# SODIMM.net
KiCad netlist of a schematic drawn in Altium Designer
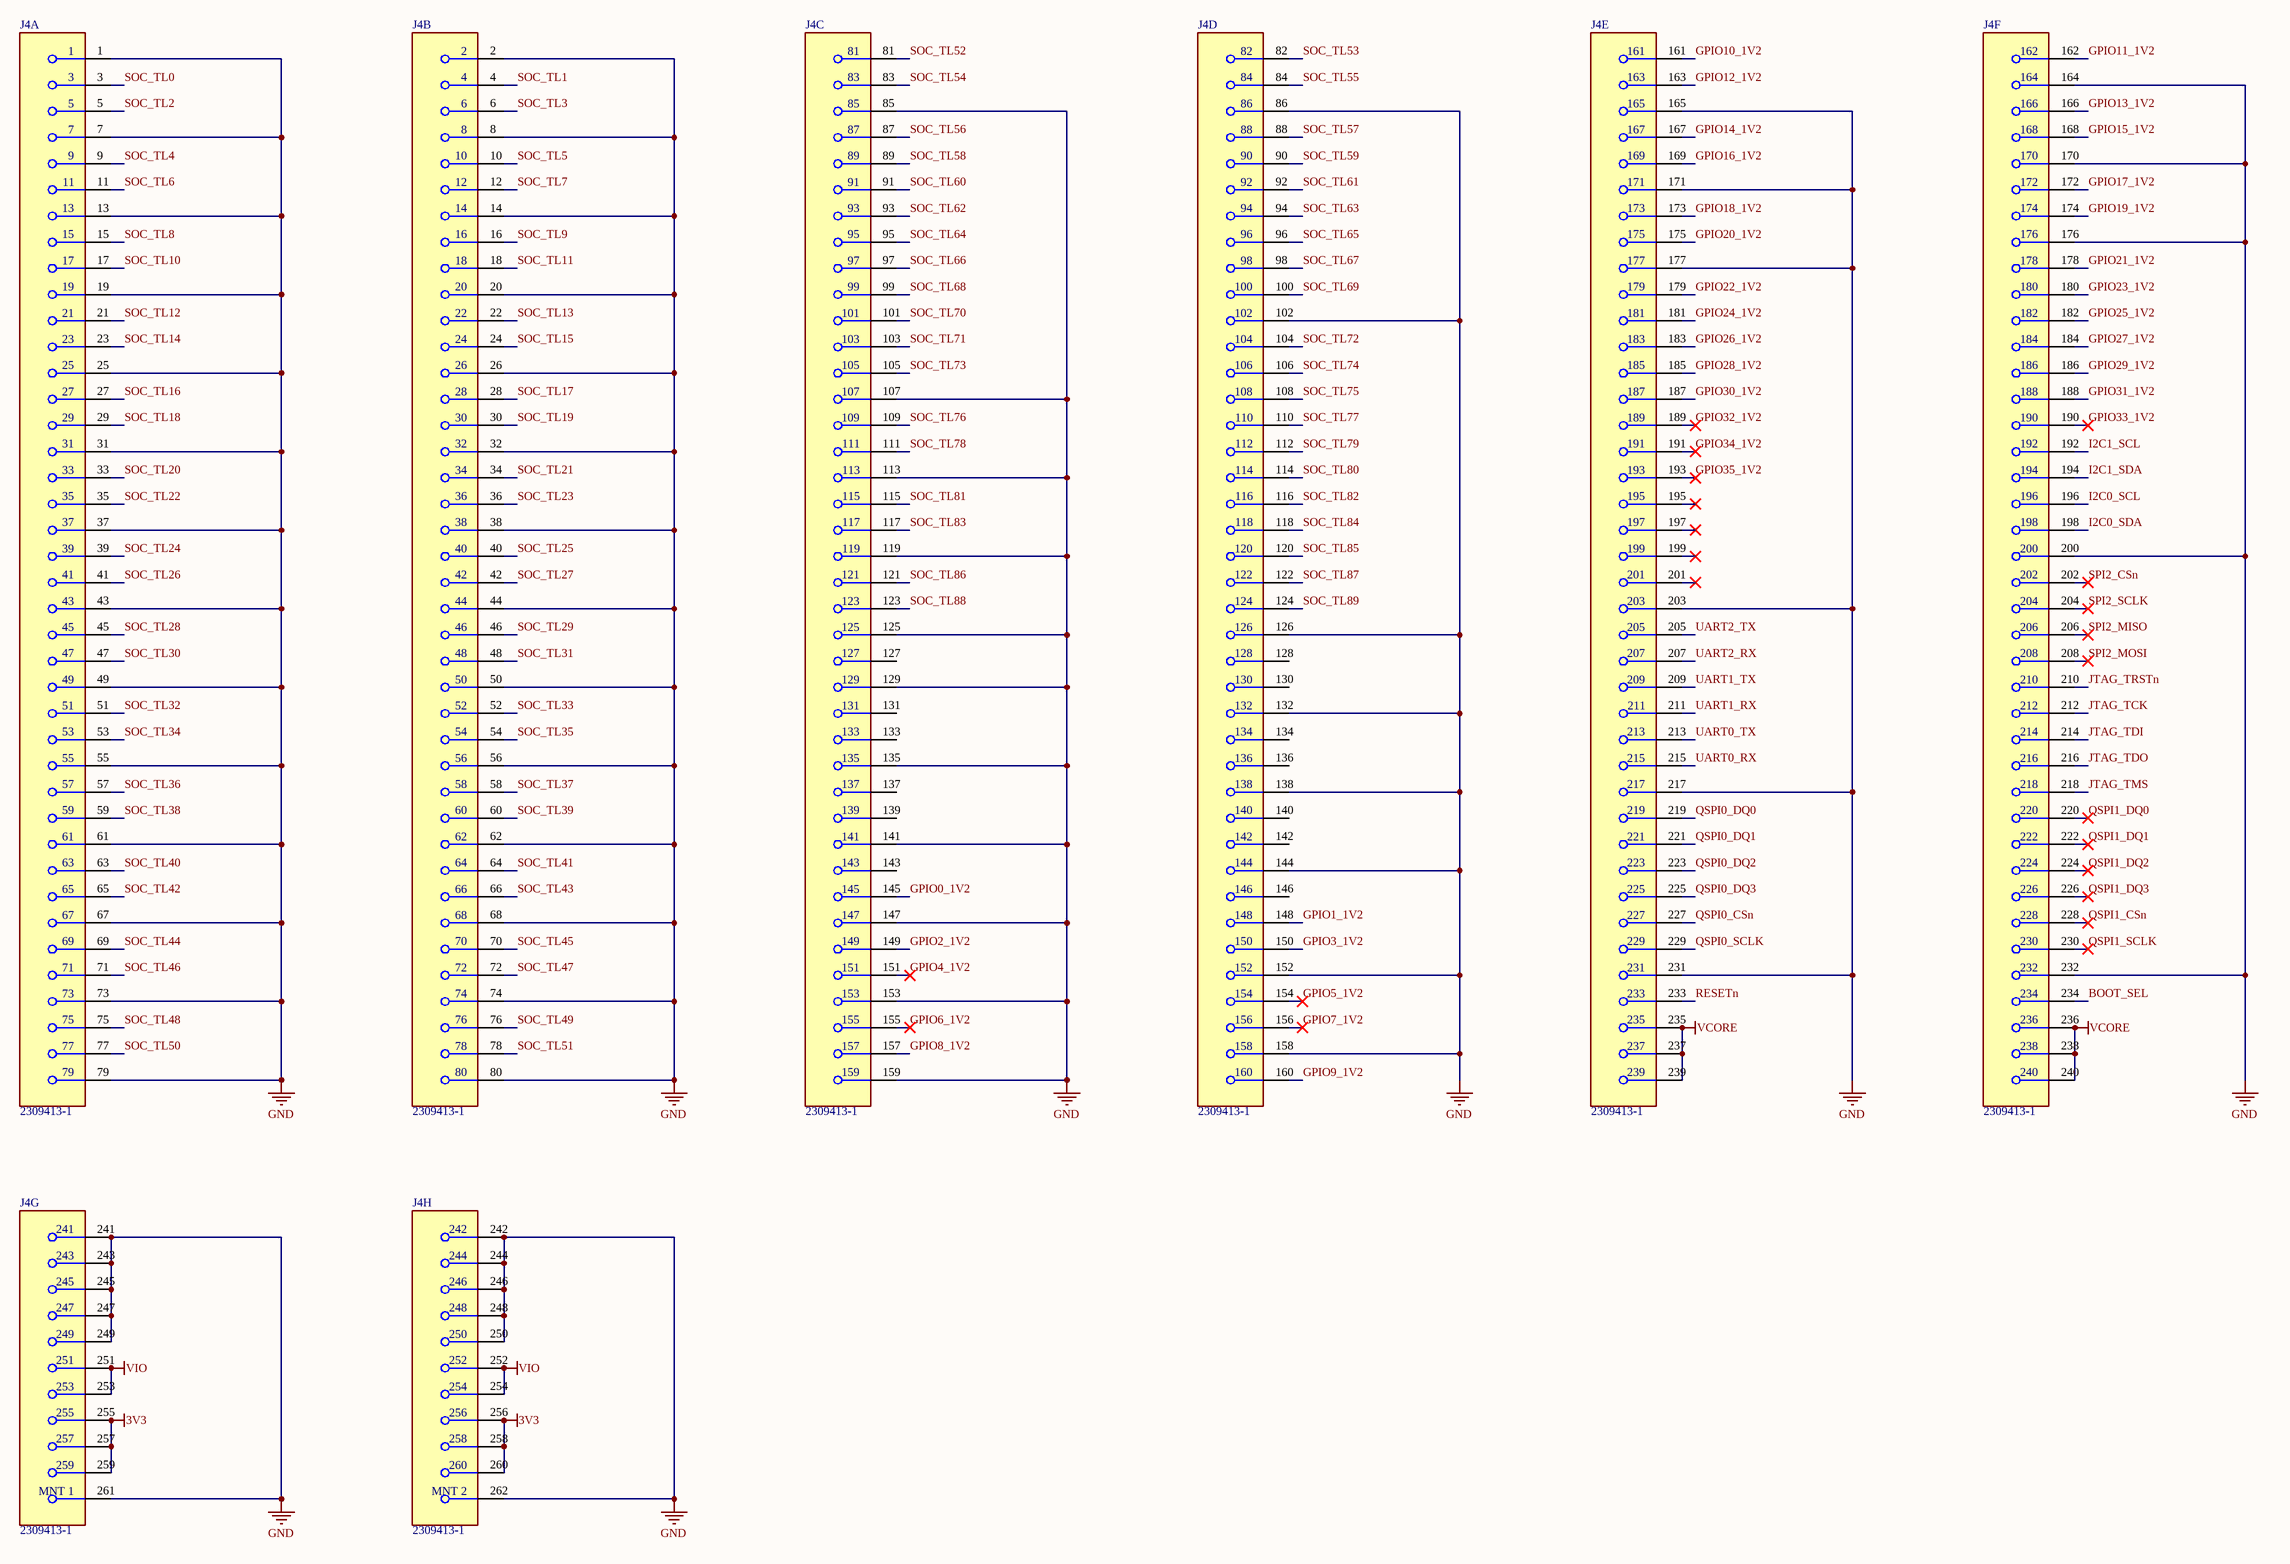
[diagram p0: SODIMM.SchDoc]

(export (version "E")
  (design (tool "Eeschema 10.0.6"))
  (components
    (comp (ref "J4")
      (value "2309413-1")
      (footprint "FP-2309413-1-MFG")
      (description "Memory Card Connector, DDR4, SODIMM, Cam-In Locking, 260 Contacts, Copper Alloy")
      (libsource (lib "UC Berkeley – EE194") (part "2309413-1"))
    )
  )
  (nets
    (net (code "1") (name "/BOOT_SEL") (class "Default")
      (node (ref "J4") (pin "234") (pinfunction "234_234") (pintype "passive"))
    )
    (net (code "2") (name "/GPIO0_1V2") (class "Default")
      (node (ref "J4") (pin "145") (pinfunction "145_145") (pintype "passive"))
    )
    (net (code "3") (name "/GPIO1_1V2") (class "Default")
      (node (ref "J4") (pin "148") (pinfunction "148_148") (pintype "passive"))
    )
    (net (code "4") (name "/GPIO2_1V2") (class "Default")
      (node (ref "J4") (pin "149") (pinfunction "149_149") (pintype "passive"))
    )
    (net (code "5") (name "/GPIO3_1V2") (class "Default")
      (node (ref "J4") (pin "150") (pinfunction "150_150") (pintype "passive"))
    )
    (net (code "6") (name "/GPIO4_1V2") (class "Default")
      (node (ref "J4") (pin "151") (pinfunction "151_151") (pintype "passive+no_connect"))
    )
    (net (code "7") (name "/GPIO5_1V2") (class "Default")
      (node (ref "J4") (pin "154") (pinfunction "154_154") (pintype "passive+no_connect"))
    )
    (net (code "8") (name "/GPIO6_1V2") (class "Default")
      (node (ref "J4") (pin "155") (pinfunction "155_155") (pintype "passive+no_connect"))
    )
    (net (code "9") (name "/GPIO7_1V2") (class "Default")
      (node (ref "J4") (pin "156") (pinfunction "156_156") (pintype "passive+no_connect"))
    )
    (net (code "10") (name "/GPIO8_1V2") (class "Default")
      (node (ref "J4") (pin "157") (pinfunction "157_157") (pintype "passive"))
    )
    (net (code "11") (name "/GPIO9_1V2") (class "Default")
      (node (ref "J4") (pin "160") (pinfunction "160_160") (pintype "passive"))
    )
    (net (code "12") (name "/GPIO10_1V2") (class "Default")
      (node (ref "J4") (pin "161") (pinfunction "161_161") (pintype "passive"))
    )
    (net (code "13") (name "/GPIO11_1V2") (class "Default")
      (node (ref "J4") (pin "162") (pinfunction "162_162") (pintype "passive"))
    )
    (net (code "14") (name "/GPIO12_1V2") (class "Default")
      (node (ref "J4") (pin "163") (pinfunction "163_163") (pintype "passive"))
    )
    (net (code "15") (name "/GPIO13_1V2") (class "Default")
      (node (ref "J4") (pin "166") (pinfunction "166_166") (pintype "passive"))
    )
    (net (code "16") (name "/GPIO14_1V2") (class "Default")
      (node (ref "J4") (pin "167") (pinfunction "167_167") (pintype "passive"))
    )
    (net (code "17") (name "/GPIO15_1V2") (class "Default")
      (node (ref "J4") (pin "168") (pinfunction "168_168") (pintype "passive"))
    )
    (net (code "18") (name "/GPIO16_1V2") (class "Default")
      (node (ref "J4") (pin "169") (pinfunction "169_169") (pintype "passive"))
    )
    (net (code "19") (name "/GPIO17_1V2") (class "Default")
      (node (ref "J4") (pin "172") (pinfunction "172_172") (pintype "passive"))
    )
    (net (code "20") (name "/GPIO18_1V2") (class "Default")
      (node (ref "J4") (pin "173") (pinfunction "173_173") (pintype "passive"))
    )
    (net (code "21") (name "/GPIO19_1V2") (class "Default")
      (node (ref "J4") (pin "174") (pinfunction "174_174") (pintype "passive"))
    )
    (net (code "22") (name "/GPIO20_1V2") (class "Default")
      (node (ref "J4") (pin "175") (pinfunction "175_175") (pintype "passive"))
    )
    (net (code "23") (name "/GPIO21_1V2") (class "Default")
      (node (ref "J4") (pin "178") (pinfunction "178_178") (pintype "passive"))
    )
    (net (code "24") (name "/GPIO22_1V2") (class "Default")
      (node (ref "J4") (pin "179") (pinfunction "179_179") (pintype "passive"))
    )
    (net (code "25") (name "/GPIO23_1V2") (class "Default")
      (node (ref "J4") (pin "180") (pinfunction "180_180") (pintype "passive"))
    )
    (net (code "26") (name "/GPIO24_1V2") (class "Default")
      (node (ref "J4") (pin "181") (pinfunction "181_181") (pintype "passive"))
    )
    (net (code "27") (name "/GPIO25_1V2") (class "Default")
      (node (ref "J4") (pin "182") (pinfunction "182_182") (pintype "passive"))
    )
    (net (code "28") (name "/GPIO26_1V2") (class "Default")
      (node (ref "J4") (pin "183") (pinfunction "183_183") (pintype "passive"))
    )
    (net (code "29") (name "/GPIO27_1V2") (class "Default")
      (node (ref "J4") (pin "184") (pinfunction "184_184") (pintype "passive"))
    )
    (net (code "30") (name "/GPIO28_1V2") (class "Default")
      (node (ref "J4") (pin "185") (pinfunction "185_185") (pintype "passive"))
    )
    (net (code "31") (name "/GPIO29_1V2") (class "Default")
      (node (ref "J4") (pin "186") (pinfunction "186_186") (pintype "passive"))
    )
    (net (code "32") (name "/GPIO30_1V2") (class "Default")
      (node (ref "J4") (pin "187") (pinfunction "187_187") (pintype "passive"))
    )
    (net (code "33") (name "/GPIO31_1V2") (class "Default")
      (node (ref "J4") (pin "188") (pinfunction "188_188") (pintype "passive"))
    )
    (net (code "34") (name "/GPIO32_1V2") (class "Default")
      (node (ref "J4") (pin "189") (pinfunction "189_189") (pintype "passive+no_connect"))
    )
    (net (code "35") (name "/GPIO33_1V2") (class "Default")
      (node (ref "J4") (pin "190") (pinfunction "190_190") (pintype "passive+no_connect"))
    )
    (net (code "36") (name "/GPIO34_1V2") (class "Default")
      (node (ref "J4") (pin "191") (pinfunction "191_191") (pintype "passive+no_connect"))
    )
    (net (code "37") (name "/GPIO35_1V2") (class "Default")
      (node (ref "J4") (pin "193") (pinfunction "193_193") (pintype "passive+no_connect"))
    )
    (net (code "38") (name "/I2C0_SCL") (class "Default")
      (node (ref "J4") (pin "196") (pinfunction "196_196") (pintype "passive"))
    )
    (net (code "39") (name "/I2C0_SDA") (class "Default")
      (node (ref "J4") (pin "198") (pinfunction "198_198") (pintype "passive"))
    )
    (net (code "40") (name "/I2C1_SCL") (class "Default")
      (node (ref "J4") (pin "192") (pinfunction "192_192") (pintype "passive"))
    )
    (net (code "41") (name "/I2C1_SDA") (class "Default")
      (node (ref "J4") (pin "194") (pinfunction "194_194") (pintype "passive"))
    )
    (net (code "42") (name "/JTAG_TCK") (class "Default")
      (node (ref "J4") (pin "212") (pinfunction "212_212") (pintype "passive"))
    )
    (net (code "43") (name "/JTAG_TDI") (class "Default")
      (node (ref "J4") (pin "214") (pinfunction "214_214") (pintype "passive"))
    )
    (net (code "44") (name "/JTAG_TDO") (class "Default")
      (node (ref "J4") (pin "216") (pinfunction "216_216") (pintype "passive"))
    )
    (net (code "45") (name "/JTAG_TMS") (class "Default")
      (node (ref "J4") (pin "218") (pinfunction "218_218") (pintype "passive"))
    )
    (net (code "46") (name "/JTAG_TRSTn") (class "Default")
      (node (ref "J4") (pin "210") (pinfunction "210_210") (pintype "passive"))
    )
    (net (code "47") (name "/QSPI0_CSn") (class "Default")
      (node (ref "J4") (pin "227") (pinfunction "227_227") (pintype "passive"))
    )
    (net (code "48") (name "/QSPI0_DQ0") (class "Default")
      (node (ref "J4") (pin "219") (pinfunction "219_219") (pintype "passive"))
    )
    (net (code "49") (name "/QSPI0_DQ1") (class "Default")
      (node (ref "J4") (pin "221") (pinfunction "221_221") (pintype "passive"))
    )
    (net (code "50") (name "/QSPI0_DQ2") (class "Default")
      (node (ref "J4") (pin "223") (pinfunction "223_223") (pintype "passive"))
    )
    (net (code "51") (name "/QSPI0_DQ3") (class "Default")
      (node (ref "J4") (pin "225") (pinfunction "225_225") (pintype "passive"))
    )
    (net (code "52") (name "/QSPI0_SCLK") (class "Default")
      (node (ref "J4") (pin "229") (pinfunction "229_229") (pintype "passive"))
    )
    (net (code "53") (name "/QSPI1_CSn") (class "Default")
      (node (ref "J4") (pin "228") (pinfunction "228_228") (pintype "passive+no_connect"))
    )
    (net (code "54") (name "/QSPI1_DQ0") (class "Default")
      (node (ref "J4") (pin "220") (pinfunction "220_220") (pintype "passive+no_connect"))
    )
    (net (code "55") (name "/QSPI1_DQ1") (class "Default")
      (node (ref "J4") (pin "222") (pinfunction "222_222") (pintype "passive+no_connect"))
    )
    (net (code "56") (name "/QSPI1_DQ2") (class "Default")
      (node (ref "J4") (pin "224") (pinfunction "224_224") (pintype "passive+no_connect"))
    )
    (net (code "57") (name "/QSPI1_DQ3") (class "Default")
      (node (ref "J4") (pin "226") (pinfunction "226_226") (pintype "passive+no_connect"))
    )
    (net (code "58") (name "/QSPI1_SCLK") (class "Default")
      (node (ref "J4") (pin "230") (pinfunction "230_230") (pintype "passive+no_connect"))
    )
    (net (code "59") (name "/RESETn") (class "Default")
      (node (ref "J4") (pin "233") (pinfunction "233_233") (pintype "passive"))
    )
    (net (code "60") (name "/SOC_TL0") (class "Default")
      (node (ref "J4") (pin "3") (pinfunction "3_3") (pintype "passive"))
    )
    (net (code "61") (name "/SOC_TL1") (class "Default")
      (node (ref "J4") (pin "4") (pinfunction "4_4") (pintype "passive"))
    )
    (net (code "62") (name "/SOC_TL2") (class "Default")
      (node (ref "J4") (pin "5") (pinfunction "5_5") (pintype "passive"))
    )
    (net (code "63") (name "/SOC_TL3") (class "Default")
      (node (ref "J4") (pin "6") (pinfunction "6_6") (pintype "passive"))
    )
    (net (code "64") (name "/SOC_TL4") (class "Default")
      (node (ref "J4") (pin "9") (pinfunction "9_9") (pintype "passive"))
    )
    (net (code "65") (name "/SOC_TL5") (class "Default")
      (node (ref "J4") (pin "10") (pinfunction "10_10") (pintype "passive"))
    )
    (net (code "66") (name "/SOC_TL6") (class "Default")
      (node (ref "J4") (pin "11") (pinfunction "11_11") (pintype "passive"))
    )
    (net (code "67") (name "/SOC_TL7") (class "Default")
      (node (ref "J4") (pin "12") (pinfunction "12_12") (pintype "passive"))
    )
    (net (code "68") (name "/SOC_TL8") (class "Default")
      (node (ref "J4") (pin "15") (pinfunction "15_15") (pintype "passive"))
    )
    (net (code "69") (name "/SOC_TL9") (class "Default")
      (node (ref "J4") (pin "16") (pinfunction "16_16") (pintype "passive"))
    )
    (net (code "70") (name "/SOC_TL10") (class "Default")
      (node (ref "J4") (pin "17") (pinfunction "17_17") (pintype "passive"))
    )
    (net (code "71") (name "/SOC_TL11") (class "Default")
      (node (ref "J4") (pin "18") (pinfunction "18_18") (pintype "passive"))
    )
    (net (code "72") (name "/SOC_TL12") (class "Default")
      (node (ref "J4") (pin "21") (pinfunction "21_21") (pintype "passive"))
    )
    (net (code "73") (name "/SOC_TL13") (class "Default")
      (node (ref "J4") (pin "22") (pinfunction "22_22") (pintype "passive"))
    )
    (net (code "74") (name "/SOC_TL14") (class "Default")
      (node (ref "J4") (pin "23") (pinfunction "23_23") (pintype "passive"))
    )
    (net (code "75") (name "/SOC_TL15") (class "Default")
      (node (ref "J4") (pin "24") (pinfunction "24_24") (pintype "passive"))
    )
    (net (code "76") (name "/SOC_TL16") (class "Default")
      (node (ref "J4") (pin "27") (pinfunction "27_27") (pintype "passive"))
    )
    (net (code "77") (name "/SOC_TL17") (class "Default")
      (node (ref "J4") (pin "28") (pinfunction "28_28") (pintype "passive"))
    )
    (net (code "78") (name "/SOC_TL18") (class "Default")
      (node (ref "J4") (pin "29") (pinfunction "29_29") (pintype "passive"))
    )
    (net (code "79") (name "/SOC_TL19") (class "Default")
      (node (ref "J4") (pin "30") (pinfunction "30_30") (pintype "passive"))
    )
    (net (code "80") (name "/SOC_TL20") (class "Default")
      (node (ref "J4") (pin "33") (pinfunction "33_33") (pintype "passive"))
    )
    (net (code "81") (name "/SOC_TL21") (class "Default")
      (node (ref "J4") (pin "34") (pinfunction "34_34") (pintype "passive"))
    )
    (net (code "82") (name "/SOC_TL22") (class "Default")
      (node (ref "J4") (pin "35") (pinfunction "35_35") (pintype "passive"))
    )
    (net (code "83") (name "/SOC_TL23") (class "Default")
      (node (ref "J4") (pin "36") (pinfunction "36_36") (pintype "passive"))
    )
    (net (code "84") (name "/SOC_TL24") (class "Default")
      (node (ref "J4") (pin "39") (pinfunction "39_39") (pintype "passive"))
    )
    (net (code "85") (name "/SOC_TL25") (class "Default")
      (node (ref "J4") (pin "40") (pinfunction "40_40") (pintype "passive"))
    )
    (net (code "86") (name "/SOC_TL26") (class "Default")
      (node (ref "J4") (pin "41") (pinfunction "41_41") (pintype "passive"))
    )
    (net (code "87") (name "/SOC_TL27") (class "Default")
      (node (ref "J4") (pin "42") (pinfunction "42_42") (pintype "passive"))
    )
    (net (code "88") (name "/SOC_TL28") (class "Default")
      (node (ref "J4") (pin "45") (pinfunction "45_45") (pintype "passive"))
    )
    (net (code "89") (name "/SOC_TL29") (class "Default")
      (node (ref "J4") (pin "46") (pinfunction "46_46") (pintype "passive"))
    )
    (net (code "90") (name "/SOC_TL30") (class "Default")
      (node (ref "J4") (pin "47") (pinfunction "47_47") (pintype "passive"))
    )
    (net (code "91") (name "/SOC_TL31") (class "Default")
      (node (ref "J4") (pin "48") (pinfunction "48_48") (pintype "passive"))
    )
    (net (code "92") (name "/SOC_TL32") (class "Default")
      (node (ref "J4") (pin "51") (pinfunction "51_51") (pintype "passive"))
    )
    (net (code "93") (name "/SOC_TL33") (class "Default")
      (node (ref "J4") (pin "52") (pinfunction "52_52") (pintype "passive"))
    )
    (net (code "94") (name "/SOC_TL34") (class "Default")
      (node (ref "J4") (pin "53") (pinfunction "53_53") (pintype "passive"))
    )
    (net (code "95") (name "/SOC_TL35") (class "Default")
      (node (ref "J4") (pin "54") (pinfunction "54_54") (pintype "passive"))
    )
    (net (code "96") (name "/SOC_TL36") (class "Default")
      (node (ref "J4") (pin "57") (pinfunction "57_57") (pintype "passive"))
    )
    (net (code "97") (name "/SOC_TL37") (class "Default")
      (node (ref "J4") (pin "58") (pinfunction "58_58") (pintype "passive"))
    )
    (net (code "98") (name "/SOC_TL38") (class "Default")
      (node (ref "J4") (pin "59") (pinfunction "59_59") (pintype "passive"))
    )
    (net (code "99") (name "/SOC_TL39") (class "Default")
      (node (ref "J4") (pin "60") (pinfunction "60_60") (pintype "passive"))
    )
    (net (code "100") (name "/SOC_TL40") (class "Default")
      (node (ref "J4") (pin "63") (pinfunction "63_63") (pintype "passive"))
    )
    (net (code "101") (name "/SOC_TL41") (class "Default")
      (node (ref "J4") (pin "64") (pinfunction "64_64") (pintype "passive"))
    )
    (net (code "102") (name "/SOC_TL42") (class "Default")
      (node (ref "J4") (pin "65") (pinfunction "65_65") (pintype "passive"))
    )
    (net (code "103") (name "/SOC_TL43") (class "Default")
      (node (ref "J4") (pin "66") (pinfunction "66_66") (pintype "passive"))
    )
    (net (code "104") (name "/SOC_TL44") (class "Default")
      (node (ref "J4") (pin "69") (pinfunction "69_69") (pintype "passive"))
    )
    (net (code "105") (name "/SOC_TL45") (class "Default")
      (node (ref "J4") (pin "70") (pinfunction "70_70") (pintype "passive"))
    )
    (net (code "106") (name "/SOC_TL46") (class "Default")
      (node (ref "J4") (pin "71") (pinfunction "71_71") (pintype "passive"))
    )
    (net (code "107") (name "/SOC_TL47") (class "Default")
      (node (ref "J4") (pin "72") (pinfunction "72_72") (pintype "passive"))
    )
    (net (code "108") (name "/SOC_TL48") (class "Default")
      (node (ref "J4") (pin "75") (pinfunction "75_75") (pintype "passive"))
    )
    (net (code "109") (name "/SOC_TL49") (class "Default")
      (node (ref "J4") (pin "76") (pinfunction "76_76") (pintype "passive"))
    )
    (net (code "110") (name "/SOC_TL50") (class "Default")
      (node (ref "J4") (pin "77") (pinfunction "77_77") (pintype "passive"))
    )
    (net (code "111") (name "/SOC_TL51") (class "Default")
      (node (ref "J4") (pin "78") (pinfunction "78_78") (pintype "passive"))
    )
    (net (code "112") (name "/SOC_TL52") (class "Default")
      (node (ref "J4") (pin "81") (pinfunction "81_81") (pintype "passive"))
    )
    (net (code "113") (name "/SOC_TL53") (class "Default")
      (node (ref "J4") (pin "82") (pinfunction "82_82") (pintype "passive"))
    )
    (net (code "114") (name "/SOC_TL54") (class "Default")
      (node (ref "J4") (pin "83") (pinfunction "83_83") (pintype "passive"))
    )
    (net (code "115") (name "/SOC_TL55") (class "Default")
      (node (ref "J4") (pin "84") (pinfunction "84_84") (pintype "passive"))
    )
    (net (code "116") (name "/SOC_TL56") (class "Default")
      (node (ref "J4") (pin "87") (pinfunction "87_87") (pintype "passive"))
    )
    (net (code "117") (name "/SOC_TL57") (class "Default")
      (node (ref "J4") (pin "88") (pinfunction "88_88") (pintype "passive"))
    )
    (net (code "118") (name "/SOC_TL58") (class "Default")
      (node (ref "J4") (pin "89") (pinfunction "89_89") (pintype "passive"))
    )
    (net (code "119") (name "/SOC_TL59") (class "Default")
      (node (ref "J4") (pin "90") (pinfunction "90_90") (pintype "passive"))
    )
    (net (code "120") (name "/SOC_TL60") (class "Default")
      (node (ref "J4") (pin "91") (pinfunction "91_91") (pintype "passive"))
    )
    (net (code "121") (name "/SOC_TL61") (class "Default")
      (node (ref "J4") (pin "92") (pinfunction "92_92") (pintype "passive"))
    )
    (net (code "122") (name "/SOC_TL62") (class "Default")
      (node (ref "J4") (pin "93") (pinfunction "93_93") (pintype "passive"))
    )
    (net (code "123") (name "/SOC_TL63") (class "Default")
      (node (ref "J4") (pin "94") (pinfunction "94_94") (pintype "passive"))
    )
    (net (code "124") (name "/SOC_TL64") (class "Default")
      (node (ref "J4") (pin "95") (pinfunction "95_95") (pintype "passive"))
    )
    (net (code "125") (name "/SOC_TL65") (class "Default")
      (node (ref "J4") (pin "96") (pinfunction "96_96") (pintype "passive"))
    )
    (net (code "126") (name "/SOC_TL66") (class "Default")
      (node (ref "J4") (pin "97") (pinfunction "97_97") (pintype "passive"))
    )
    (net (code "127") (name "/SOC_TL67") (class "Default")
      (node (ref "J4") (pin "98") (pinfunction "98_98") (pintype "passive"))
    )
    (net (code "128") (name "/SOC_TL68") (class "Default")
      (node (ref "J4") (pin "99") (pinfunction "99_99") (pintype "passive"))
    )
    (net (code "129") (name "/SOC_TL69") (class "Default")
      (node (ref "J4") (pin "100") (pinfunction "100_100") (pintype "passive"))
    )
    (net (code "130") (name "/SOC_TL70") (class "Default")
      (node (ref "J4") (pin "101") (pinfunction "101_101") (pintype "passive"))
    )
    (net (code "131") (name "/SOC_TL71") (class "Default")
      (node (ref "J4") (pin "103") (pinfunction "103_103") (pintype "passive"))
    )
    (net (code "132") (name "/SOC_TL72") (class "Default")
      (node (ref "J4") (pin "104") (pinfunction "104_104") (pintype "passive"))
    )
    (net (code "133") (name "/SOC_TL73") (class "Default")
      (node (ref "J4") (pin "105") (pinfunction "105_105") (pintype "passive"))
    )
    (net (code "134") (name "/SOC_TL74") (class "Default")
      (node (ref "J4") (pin "106") (pinfunction "106_106") (pintype "passive"))
    )
    (net (code "135") (name "/SOC_TL75") (class "Default")
      (node (ref "J4") (pin "108") (pinfunction "108_108") (pintype "passive"))
    )
    (net (code "136") (name "/SOC_TL76") (class "Default")
      (node (ref "J4") (pin "109") (pinfunction "109_109") (pintype "passive"))
    )
    (net (code "137") (name "/SOC_TL77") (class "Default")
      (node (ref "J4") (pin "110") (pinfunction "110_110") (pintype "passive"))
    )
    (net (code "138") (name "/SOC_TL78") (class "Default")
      (node (ref "J4") (pin "111") (pinfunction "111_111") (pintype "passive"))
    )
    (net (code "139") (name "/SOC_TL79") (class "Default")
      (node (ref "J4") (pin "112") (pinfunction "112_112") (pintype "passive"))
    )
    (net (code "140") (name "/SOC_TL80") (class "Default")
      (node (ref "J4") (pin "114") (pinfunction "114_114") (pintype "passive"))
    )
    (net (code "141") (name "/SOC_TL81") (class "Default")
      (node (ref "J4") (pin "115") (pinfunction "115_115") (pintype "passive"))
    )
    (net (code "142") (name "/SOC_TL82") (class "Default")
      (node (ref "J4") (pin "116") (pinfunction "116_116") (pintype "passive"))
    )
    (net (code "143") (name "/SOC_TL83") (class "Default")
      (node (ref "J4") (pin "117") (pinfunction "117_117") (pintype "passive"))
    )
    (net (code "144") (name "/SOC_TL84") (class "Default")
      (node (ref "J4") (pin "118") (pinfunction "118_118") (pintype "passive"))
    )
    (net (code "145") (name "/SOC_TL85") (class "Default")
      (node (ref "J4") (pin "120") (pinfunction "120_120") (pintype "passive"))
    )
    (net (code "146") (name "/SOC_TL86") (class "Default")
      (node (ref "J4") (pin "121") (pinfunction "121_121") (pintype "passive"))
    )
    (net (code "147") (name "/SOC_TL87") (class "Default")
      (node (ref "J4") (pin "122") (pinfunction "122_122") (pintype "passive"))
    )
    (net (code "148") (name "/SOC_TL88") (class "Default")
      (node (ref "J4") (pin "123") (pinfunction "123_123") (pintype "passive"))
    )
    (net (code "149") (name "/SOC_TL89") (class "Default")
      (node (ref "J4") (pin "124") (pinfunction "124_124") (pintype "passive"))
    )
    (net (code "150") (name "/SPI2_CSn") (class "Default")
      (node (ref "J4") (pin "202") (pinfunction "202_202") (pintype "passive+no_connect"))
    )
    (net (code "151") (name "/SPI2_MISO") (class "Default")
      (node (ref "J4") (pin "206") (pinfunction "206_206") (pintype "passive+no_connect"))
    )
    (net (code "152") (name "/SPI2_MOSI") (class "Default")
      (node (ref "J4") (pin "208") (pinfunction "208_208") (pintype "passive+no_connect"))
    )
    (net (code "153") (name "/SPI2_SCLK") (class "Default")
      (node (ref "J4") (pin "204") (pinfunction "204_204") (pintype "passive+no_connect"))
    )
    (net (code "154") (name "/UART0_RX") (class "Default")
      (node (ref "J4") (pin "215") (pinfunction "215_215") (pintype "passive"))
    )
    (net (code "155") (name "/UART0_TX") (class "Default")
      (node (ref "J4") (pin "213") (pinfunction "213_213") (pintype "passive"))
    )
    (net (code "156") (name "/UART1_RX") (class "Default")
      (node (ref "J4") (pin "211") (pinfunction "211_211") (pintype "passive"))
    )
    (net (code "157") (name "/UART1_TX") (class "Default")
      (node (ref "J4") (pin "209") (pinfunction "209_209") (pintype "passive"))
    )
    (net (code "158") (name "/UART2_RX") (class "Default")
      (node (ref "J4") (pin "207") (pinfunction "207_207") (pintype "passive"))
    )
    (net (code "159") (name "/UART2_TX") (class "Default")
      (node (ref "J4") (pin "205") (pinfunction "205_205") (pintype "passive"))
    )
    (net (code "160") (name "3V3") (class "Default")
      (node (ref "J4") (pin "255") (pinfunction "255_255") (pintype "passive"))
      (node (ref "J4") (pin "256") (pinfunction "256_256") (pintype "passive"))
      (node (ref "J4") (pin "257") (pinfunction "257_257") (pintype "passive"))
      (node (ref "J4") (pin "258") (pinfunction "258_258") (pintype "passive"))
      (node (ref "J4") (pin "259") (pinfunction "259_259") (pintype "passive"))
      (node (ref "J4") (pin "260") (pinfunction "260_260") (pintype "passive"))
    )
    (net (code "161") (name "GND") (class "Default")
      (node (ref "J4") (pin "1") (pinfunction "1_1") (pintype "passive"))
      (node (ref "J4") (pin "102") (pinfunction "102_102") (pintype "passive"))
      (node (ref "J4") (pin "107") (pinfunction "107_107") (pintype "passive"))
      (node (ref "J4") (pin "113") (pinfunction "113_113") (pintype "passive"))
      (node (ref "J4") (pin "119") (pinfunction "119_119") (pintype "passive"))
      (node (ref "J4") (pin "125") (pinfunction "125_125") (pintype "passive"))
      (node (ref "J4") (pin "126") (pinfunction "126_126") (pintype "passive"))
      (node (ref "J4") (pin "129") (pinfunction "129_129") (pintype "passive"))
      (node (ref "J4") (pin "13") (pinfunction "13_13") (pintype "passive"))
      (node (ref "J4") (pin "132") (pinfunction "132_132") (pintype "passive"))
      (node (ref "J4") (pin "135") (pinfunction "135_135") (pintype "passive"))
      (node (ref "J4") (pin "138") (pinfunction "138_138") (pintype "passive"))
      (node (ref "J4") (pin "14") (pinfunction "14_14") (pintype "passive"))
      (node (ref "J4") (pin "141") (pinfunction "141_141") (pintype "passive"))
      (node (ref "J4") (pin "144") (pinfunction "144_144") (pintype "passive"))
      (node (ref "J4") (pin "147") (pinfunction "147_147") (pintype "passive"))
      (node (ref "J4") (pin "152") (pinfunction "152_152") (pintype "passive"))
      (node (ref "J4") (pin "153") (pinfunction "153_153") (pintype "passive"))
      (node (ref "J4") (pin "158") (pinfunction "158_158") (pintype "passive"))
      (node (ref "J4") (pin "159") (pinfunction "159_159") (pintype "passive"))
      (node (ref "J4") (pin "164") (pinfunction "164_164") (pintype "passive"))
      (node (ref "J4") (pin "165") (pinfunction "165_165") (pintype "passive"))
      (node (ref "J4") (pin "170") (pinfunction "170_170") (pintype "passive"))
      (node (ref "J4") (pin "171") (pinfunction "171_171") (pintype "passive"))
      (node (ref "J4") (pin "176") (pinfunction "176_176") (pintype "passive"))
      (node (ref "J4") (pin "177") (pinfunction "177_177") (pintype "passive"))
      (node (ref "J4") (pin "19") (pinfunction "19_19") (pintype "passive"))
      (node (ref "J4") (pin "2") (pinfunction "2_2") (pintype "passive"))
      (node (ref "J4") (pin "20") (pinfunction "20_20") (pintype "passive"))
      (node (ref "J4") (pin "200") (pinfunction "200_200") (pintype "passive"))
      (node (ref "J4") (pin "203") (pinfunction "203_203") (pintype "passive"))
      (node (ref "J4") (pin "217") (pinfunction "217_217") (pintype "passive"))
      (node (ref "J4") (pin "231") (pinfunction "231_231") (pintype "passive"))
      (node (ref "J4") (pin "232") (pinfunction "232_232") (pintype "passive"))
      (node (ref "J4") (pin "241") (pinfunction "241_241") (pintype "passive"))
      (node (ref "J4") (pin "242") (pinfunction "242_242") (pintype "passive"))
      (node (ref "J4") (pin "243") (pinfunction "243_243") (pintype "passive"))
      (node (ref "J4") (pin "244") (pinfunction "244_244") (pintype "passive"))
      (node (ref "J4") (pin "245") (pinfunction "245_245") (pintype "passive"))
      (node (ref "J4") (pin "246") (pinfunction "246_246") (pintype "passive"))
      (node (ref "J4") (pin "247") (pinfunction "247_247") (pintype "passive"))
      (node (ref "J4") (pin "248") (pinfunction "248_248") (pintype "passive"))
      (node (ref "J4") (pin "249") (pinfunction "249_249") (pintype "passive"))
      (node (ref "J4") (pin "25") (pinfunction "25_25") (pintype "passive"))
      (node (ref "J4") (pin "250") (pinfunction "250_250") (pintype "passive"))
      (node (ref "J4") (pin "26") (pinfunction "26_26") (pintype "passive"))
      (node (ref "J4") (pin "261") (pinfunction "MNT_1_261") (pintype "passive"))
      (node (ref "J4") (pin "262") (pinfunction "MNT_2_262") (pintype "passive"))
      (node (ref "J4") (pin "31") (pinfunction "31_31") (pintype "passive"))
      (node (ref "J4") (pin "32") (pinfunction "32_32") (pintype "passive"))
      (node (ref "J4") (pin "37") (pinfunction "37_37") (pintype "passive"))
      (node (ref "J4") (pin "38") (pinfunction "38_38") (pintype "passive"))
      (node (ref "J4") (pin "43") (pinfunction "43_43") (pintype "passive"))
      (node (ref "J4") (pin "44") (pinfunction "44_44") (pintype "passive"))
      (node (ref "J4") (pin "49") (pinfunction "49_49") (pintype "passive"))
      (node (ref "J4") (pin "50") (pinfunction "50_50") (pintype "passive"))
      (node (ref "J4") (pin "55") (pinfunction "55_55") (pintype "passive"))
      (node (ref "J4") (pin "56") (pinfunction "56_56") (pintype "passive"))
      (node (ref "J4") (pin "61") (pinfunction "61_61") (pintype "passive"))
      (node (ref "J4") (pin "62") (pinfunction "62_62") (pintype "passive"))
      (node (ref "J4") (pin "67") (pinfunction "67_67") (pintype "passive"))
      (node (ref "J4") (pin "68") (pinfunction "68_68") (pintype "passive"))
      (node (ref "J4") (pin "7") (pinfunction "7_7") (pintype "passive"))
      (node (ref "J4") (pin "73") (pinfunction "73_73") (pintype "passive"))
      (node (ref "J4") (pin "74") (pinfunction "74_74") (pintype "passive"))
      (node (ref "J4") (pin "79") (pinfunction "79_79") (pintype "passive"))
      (node (ref "J4") (pin "8") (pinfunction "8_8") (pintype "passive"))
      (node (ref "J4") (pin "80") (pinfunction "80_80") (pintype "passive"))
      (node (ref "J4") (pin "85") (pinfunction "85_85") (pintype "passive"))
      (node (ref "J4") (pin "86") (pinfunction "86_86") (pintype "passive"))
    )
    (net (code "162") (name "VCORE") (class "Default")
      (node (ref "J4") (pin "235") (pinfunction "235_235") (pintype "passive"))
      (node (ref "J4") (pin "236") (pinfunction "236_236") (pintype "passive"))
      (node (ref "J4") (pin "237") (pinfunction "237_237") (pintype "passive"))
      (node (ref "J4") (pin "238") (pinfunction "238_238") (pintype "passive"))
      (node (ref "J4") (pin "239") (pinfunction "239_239") (pintype "passive"))
      (node (ref "J4") (pin "240") (pinfunction "240_240") (pintype "passive"))
    )
    (net (code "163") (name "VIO") (class "Default")
      (node (ref "J4") (pin "251") (pinfunction "251_251") (pintype "passive"))
      (node (ref "J4") (pin "252") (pinfunction "252_252") (pintype "passive"))
      (node (ref "J4") (pin "253") (pinfunction "253_253") (pintype "passive"))
      (node (ref "J4") (pin "254") (pinfunction "254_254") (pintype "passive"))
    )
    (net (code "164") (name "unconnected-(J4-Pad127)") (class "Default")
      (node (ref "J4") (pin "127") (pinfunction "127_127") (pintype "passive"))
    )
    (net (code "165") (name "unconnected-(J4-Pad128)") (class "Default")
      (node (ref "J4") (pin "128") (pinfunction "128_128") (pintype "passive"))
    )
    (net (code "166") (name "unconnected-(J4-Pad130)") (class "Default")
      (node (ref "J4") (pin "130") (pinfunction "130_130") (pintype "passive"))
    )
    (net (code "167") (name "unconnected-(J4-Pad131)") (class "Default")
      (node (ref "J4") (pin "131") (pinfunction "131_131") (pintype "passive"))
    )
    (net (code "168") (name "unconnected-(J4-Pad133)") (class "Default")
      (node (ref "J4") (pin "133") (pinfunction "133_133") (pintype "passive"))
    )
    (net (code "169") (name "unconnected-(J4-Pad134)") (class "Default")
      (node (ref "J4") (pin "134") (pinfunction "134_134") (pintype "passive"))
    )
    (net (code "170") (name "unconnected-(J4-Pad136)") (class "Default")
      (node (ref "J4") (pin "136") (pinfunction "136_136") (pintype "passive"))
    )
    (net (code "171") (name "unconnected-(J4-Pad137)") (class "Default")
      (node (ref "J4") (pin "137") (pinfunction "137_137") (pintype "passive"))
    )
    (net (code "172") (name "unconnected-(J4-Pad139)") (class "Default")
      (node (ref "J4") (pin "139") (pinfunction "139_139") (pintype "passive"))
    )
    (net (code "173") (name "unconnected-(J4-Pad140)") (class "Default")
      (node (ref "J4") (pin "140") (pinfunction "140_140") (pintype "passive"))
    )
    (net (code "174") (name "unconnected-(J4-Pad142)") (class "Default")
      (node (ref "J4") (pin "142") (pinfunction "142_142") (pintype "passive"))
    )
    (net (code "175") (name "unconnected-(J4-Pad143)") (class "Default")
      (node (ref "J4") (pin "143") (pinfunction "143_143") (pintype "passive"))
    )
    (net (code "176") (name "unconnected-(J4-Pad146)") (class "Default")
      (node (ref "J4") (pin "146") (pinfunction "146_146") (pintype "passive"))
    )
    (net (code "177") (name "unconnected-(J4-Pad195)") (class "Default")
      (node (ref "J4") (pin "195") (pinfunction "195_195") (pintype "passive+no_connect"))
    )
    (net (code "178") (name "unconnected-(J4-Pad197)") (class "Default")
      (node (ref "J4") (pin "197") (pinfunction "197_197") (pintype "passive+no_connect"))
    )
    (net (code "179") (name "unconnected-(J4-Pad199)") (class "Default")
      (node (ref "J4") (pin "199") (pinfunction "199_199") (pintype "passive+no_connect"))
    )
    (net (code "180") (name "unconnected-(J4-Pad201)") (class "Default")
      (node (ref "J4") (pin "201") (pinfunction "201_201") (pintype "passive+no_connect"))
    )
  )
)
